# rpi-can-rs485.net
KiCad netlist of a schematic drawn in EAGLE
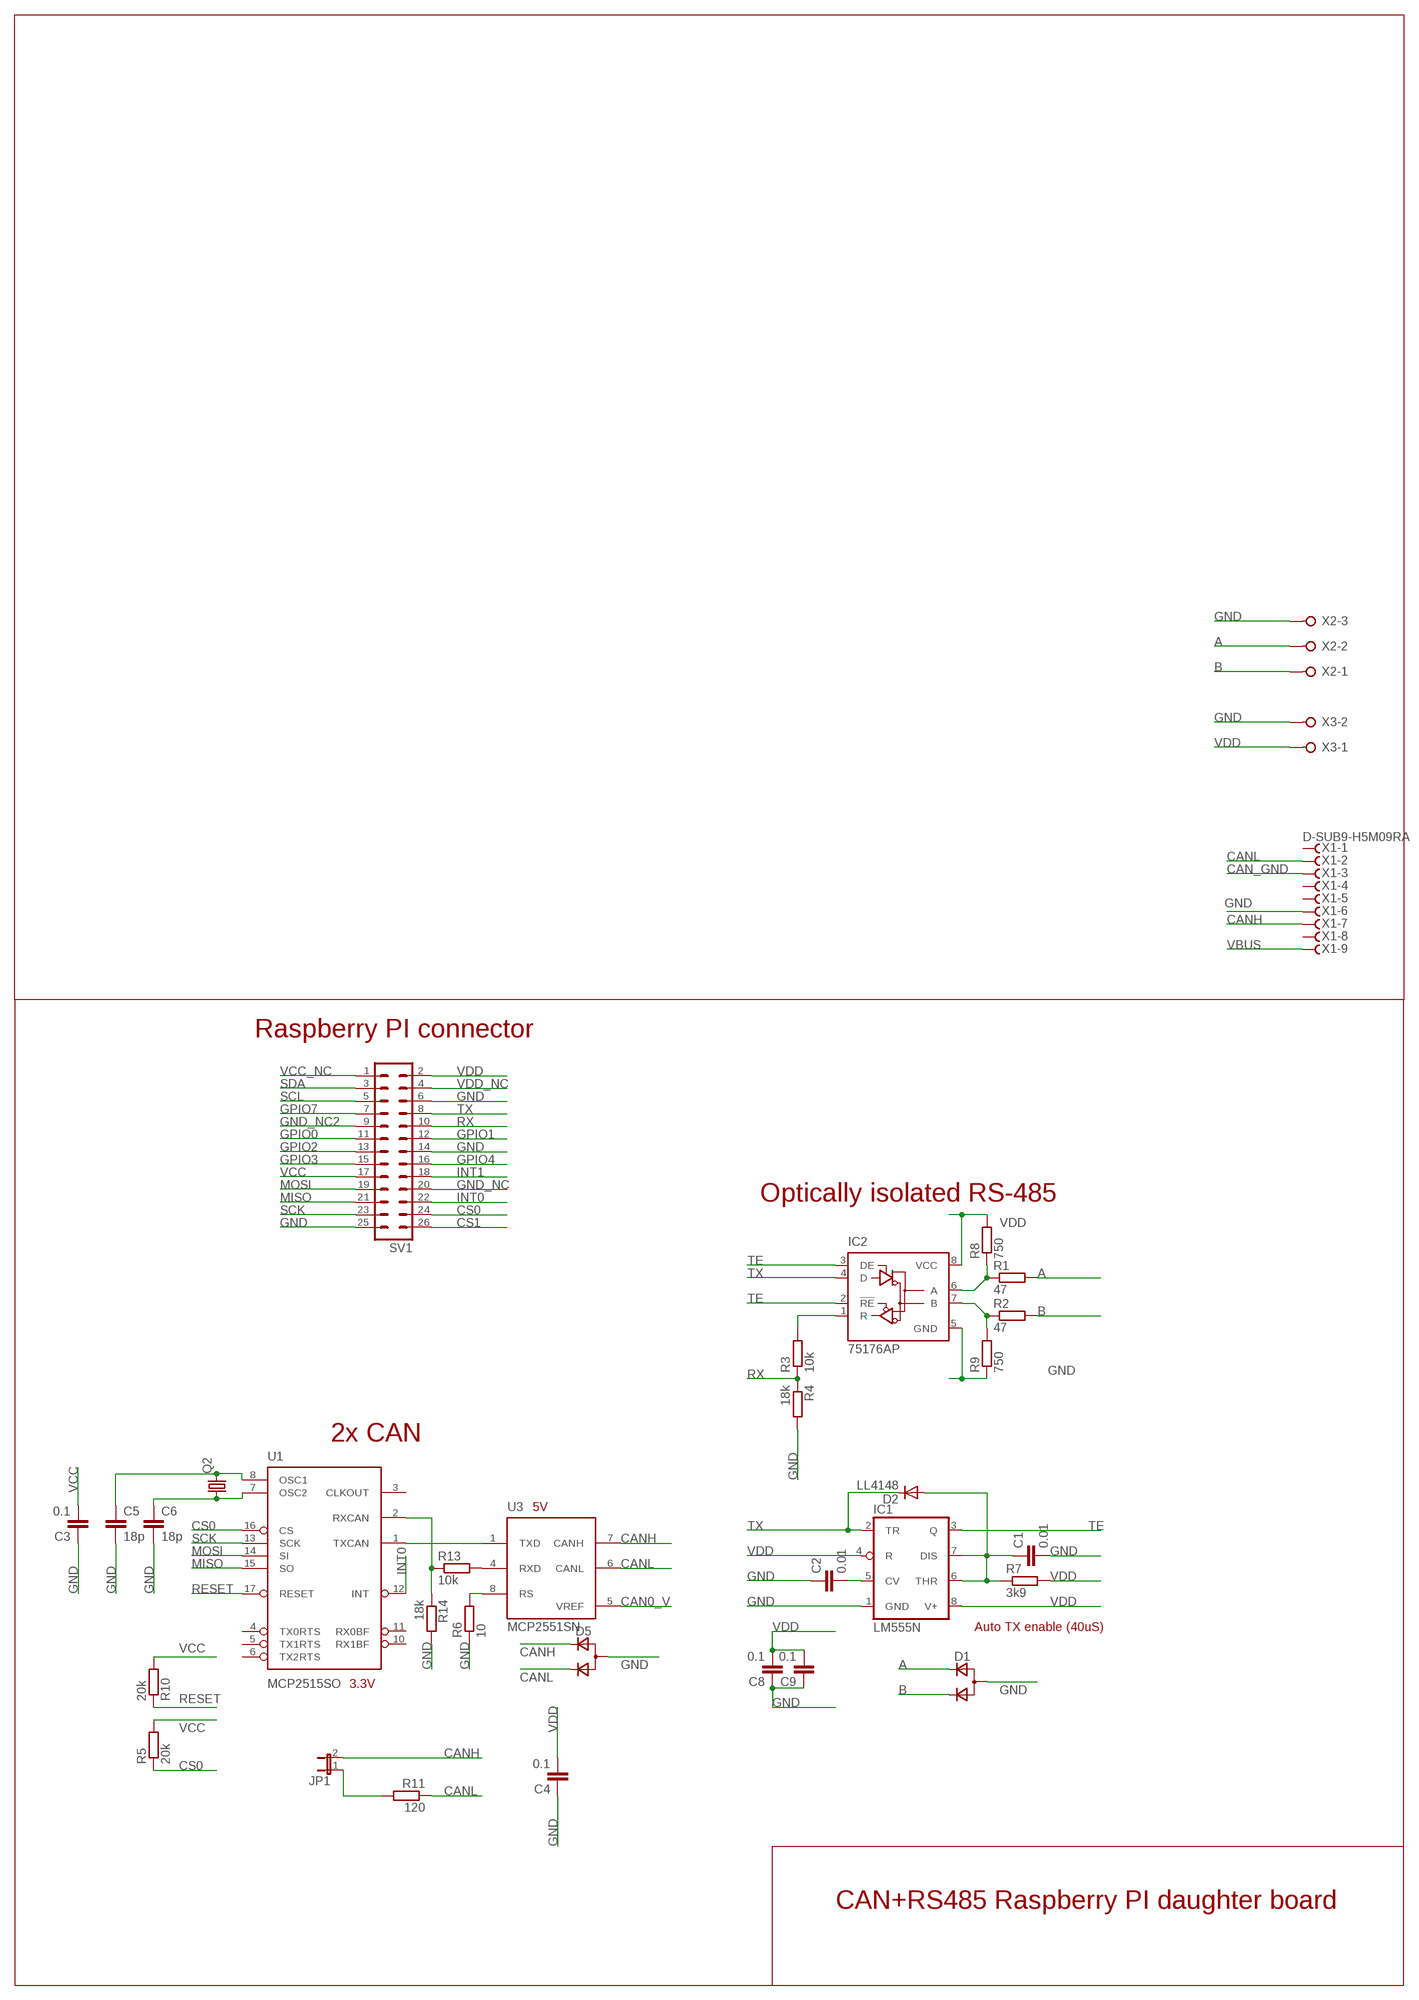
[diagram p0: schematic, sheet 1]

(export (version "E")
  (design (tool "Eeschema 10.0.6"))
  (components
    (comp (ref "C1")
      (value "0.01")
      (footprint "eagle-import:C0805")
      (libsource (lib "eagle-import") (part "C-EUC0805"))
    )
    (comp (ref "C2")
      (value "0.01")
      (footprint "eagle-import:C0805")
      (libsource (lib "eagle-import") (part "C-EUC0805"))
    )
    (comp (ref "C3")
      (value "0.1")
      (footprint "eagle-import:C0805")
      (libsource (lib "eagle-import") (part "C-EUC0805"))
    )
    (comp (ref "C4")
      (value "0.1")
      (footprint "eagle-import:C0805")
      (libsource (lib "eagle-import") (part "C-EUC0805"))
    )
    (comp (ref "C5")
      (value "18p")
      (footprint "eagle-import:C0805")
      (libsource (lib "eagle-import") (part "C-EUC0805"))
    )
    (comp (ref "C6")
      (value "18p")
      (footprint "eagle-import:C0805")
      (libsource (lib "eagle-import") (part "C-EUC0805"))
    )
    (comp (ref "C8")
      (value "0.1")
      (footprint "eagle-import:C0805")
      (libsource (lib "eagle-import") (part "C-EUC0805"))
    )
    (comp (ref "C9")
      (value "0.1")
      (footprint "eagle-import:C0805")
      (libsource (lib "eagle-import") (part "C-EUC0805"))
    )
    (comp (ref "D1")
      (value "D_2CSOT323")
      (footprint "eagle-import:SOT323")
      (libsource (lib "eagle-import") (part "D_2CSOT323"))
    )
    (comp (ref "D2")
      (value "LL4148")
      (footprint "eagle-import:SOD80C")
      (libsource (lib "eagle-import") (part "DIODE-SOD80C"))
    )
    (comp (ref "D5")
      (value "D_2CSOT323")
      (footprint "eagle-import:SOT323")
      (libsource (lib "eagle-import") (part "D_2CSOT323"))
    )
    (comp (ref "IC1")
      (value "LM555N")
      (footprint "eagle-import:DIL08")
      (libsource (lib "eagle-import") (part "555NLM"))
    )
    (comp (ref "IC2")
      (value "75176AP")
      (footprint "eagle-import:DIL08")
      (libsource (lib "eagle-import") (part "75176AP"))
    )
    (comp (ref "JP1")
      (value "JP1E")
      (footprint "eagle-import:JP1")
      (libsource (lib "eagle-import") (part "JP1E"))
    )
    (comp (ref "Q2")
      (value "CRYSTALHC49S")
      (footprint "eagle-import:HC49_S")
      (libsource (lib "eagle-import") (part "CRYSTALHC49S"))
    )
    (comp (ref "R1")
      (value "47")
      (footprint "eagle-import:R1206")
      (libsource (lib "eagle-import") (part "R-EU_R1206"))
    )
    (comp (ref "R2")
      (value "47")
      (footprint "eagle-import:R1206")
      (libsource (lib "eagle-import") (part "R-EU_R1206"))
    )
    (comp (ref "R3")
      (value "10k")
      (footprint "eagle-import:R0805")
      (libsource (lib "eagle-import") (part "R-EU_R0805"))
    )
    (comp (ref "R4")
      (value "18k")
      (footprint "eagle-import:R0805")
      (libsource (lib "eagle-import") (part "R-EU_R0805"))
    )
    (comp (ref "R5")
      (value "20k")
      (footprint "eagle-import:R0603")
      (libsource (lib "eagle-import") (part "R-EU_R0603"))
    )
    (comp (ref "R6")
      (value "10")
      (footprint "eagle-import:R0805")
      (libsource (lib "eagle-import") (part "R-EU_R0805"))
    )
    (comp (ref "R7")
      (value "3k9")
      (footprint "eagle-import:R0805")
      (libsource (lib "eagle-import") (part "R-EU_R0805"))
    )
    (comp (ref "R8")
      (value "750")
      (footprint "eagle-import:R1206")
      (libsource (lib "eagle-import") (part "R-EU_R1206"))
    )
    (comp (ref "R9")
      (value "750")
      (footprint "eagle-import:R1206")
      (libsource (lib "eagle-import") (part "R-EU_R1206"))
    )
    (comp (ref "R10")
      (value "20k")
      (footprint "eagle-import:R0805")
      (libsource (lib "eagle-import") (part "R-EU_R0805"))
    )
    (comp (ref "R11")
      (value "120")
      (footprint "eagle-import:R0805")
      (libsource (lib "eagle-import") (part "R-EU_R0805"))
    )
    (comp (ref "R13")
      (value "10k")
      (footprint "eagle-import:R0805")
      (libsource (lib "eagle-import") (part "R-EU_R0805"))
    )
    (comp (ref "R14")
      (value "18k")
      (footprint "eagle-import:R0805")
      (libsource (lib "eagle-import") (part "R-EU_R0805"))
    )
    (comp (ref "SV1")
      (value "MA13-2")
      (footprint "eagle-import:MA13-2")
      (libsource (lib "eagle-import") (part "MA13-2"))
    )
    (comp (ref "U1")
      (value "MCP2515SO")
      (footprint "eagle-import:SO-18W")
      (libsource (lib "eagle-import") (part "MCP2510SO"))
    )
    (comp (ref "U3")
      (value "MCP2551SN")
      (footprint "eagle-import:SO-08")
      (libsource (lib "eagle-import") (part "MCP2551SN"))
    )
    (comp (ref "X1")
      (value "D-SUB9-H5M09RA")
      (footprint "eagle-import:H5M09RA")
      (libsource (lib "eagle-import") (part "D-SUB9-H5M09RA"))
    )
    (comp (ref "X2")
      (value "W237-03P")
      (footprint "eagle-import:W237-133")
      (libsource (lib "eagle-import") (part "W237-03P"))
    )
    (comp (ref "X3")
      (value "W237-02P")
      (footprint "eagle-import:W237-132")
      (libsource (lib "eagle-import") (part "W237-02P"))
    )
  )
  (nets
    (net (code "1") (name "/A") (class "Default")
      (node (ref "D1") (pin "2") (pinfunction "C1_2") (pintype "passive"))
      (node (ref "R1") (pin "2") (pinfunction "2_2") (pintype "passive"))
      (node (ref "X2") (pin "2") (pinfunction "KL_2") (pintype "passive"))
    )
    (net (code "2") (name "/B") (class "Default")
      (node (ref "D1") (pin "3") (pinfunction "C2_3") (pintype "passive"))
      (node (ref "R2") (pin "2") (pinfunction "2_2") (pintype "passive"))
      (node (ref "X2") (pin "1") (pinfunction "KL_1") (pintype "passive"))
    )
    (net (code "3") (name "/CAN0_V") (class "Default")
      (node (ref "U3") (pin "5") (pinfunction "VREF_5") (pintype "power_in"))
    )
    (net (code "4") (name "/CANH") (class "Default")
      (node (ref "D5") (pin "2") (pinfunction "C1_2") (pintype "passive"))
      (node (ref "JP1") (pin "2") (pinfunction "2_2") (pintype "passive"))
      (node (ref "U3") (pin "7") (pinfunction "CANH_7") (pintype "bidirectional"))
      (node (ref "X1") (pin "7") (pinfunction "F_7") (pintype "passive"))
    )
    (net (code "5") (name "/CANL") (class "Default")
      (node (ref "D5") (pin "3") (pinfunction "C2_3") (pintype "passive"))
      (node (ref "R11") (pin "1") (pinfunction "1_1") (pintype "passive"))
      (node (ref "U3") (pin "6") (pinfunction "CANL_6") (pintype "bidirectional"))
      (node (ref "X1") (pin "2") (pinfunction "F_2") (pintype "passive"))
    )
    (net (code "6") (name "/CAN_GND") (class "Default")
      (node (ref "X1") (pin "3") (pinfunction "F_3") (pintype "passive"))
    )
    (net (code "7") (name "/CS0") (class "Default")
      (node (ref "R5") (pin "1") (pinfunction "1_1") (pintype "passive"))
      (node (ref "SV1") (pin "24") (pinfunction "24_24") (pintype "passive"))
      (node (ref "U1") (pin "16") (pinfunction "CS_16") (pintype "input"))
    )
    (net (code "8") (name "/CS1") (class "Default")
      (node (ref "SV1") (pin "26") (pinfunction "26_26") (pintype "passive"))
    )
    (net (code "9") (name "/GND") (class "Default")
      (node (ref "C1") (pin "2") (pinfunction "2_2") (pintype "passive"))
      (node (ref "C2") (pin "1") (pinfunction "1_1") (pintype "passive"))
      (node (ref "C3") (pin "1") (pinfunction "1_1") (pintype "passive"))
      (node (ref "C4") (pin "1") (pinfunction "1_1") (pintype "passive"))
      (node (ref "C5") (pin "2") (pinfunction "2_2") (pintype "passive"))
      (node (ref "C6") (pin "2") (pinfunction "2_2") (pintype "passive"))
      (node (ref "C8") (pin "1") (pinfunction "1_1") (pintype "passive"))
      (node (ref "C9") (pin "1") (pinfunction "1_1") (pintype "passive"))
      (node (ref "D1") (pin "1") (pinfunction "A_1") (pintype "passive"))
      (node (ref "D5") (pin "1") (pinfunction "A_1") (pintype "passive"))
      (node (ref "IC1") (pin "1") (pinfunction "GND_1") (pintype "power_in"))
      (node (ref "IC2") (pin "5") (pinfunction "GND_5") (pintype "power_in"))
      (node (ref "R14") (pin "2") (pinfunction "2_2") (pintype "passive"))
      (node (ref "R4") (pin "2") (pinfunction "2_2") (pintype "passive"))
      (node (ref "R6") (pin "1") (pinfunction "1_1") (pintype "passive"))
      (node (ref "R9") (pin "1") (pinfunction "1_1") (pintype "passive"))
      (node (ref "SV1") (pin "14") (pinfunction "14_14") (pintype "passive"))
      (node (ref "SV1") (pin "25") (pinfunction "25_25") (pintype "passive"))
      (node (ref "SV1") (pin "6") (pinfunction "6_6") (pintype "passive"))
      (node (ref "X1") (pin "6") (pinfunction "F_6") (pintype "passive"))
      (node (ref "X2") (pin "3") (pinfunction "KL_3") (pintype "passive"))
      (node (ref "X3") (pin "2") (pinfunction "KL_2") (pintype "passive"))
    )
    (net (code "10") (name "/GND_NC") (class "Default")
      (node (ref "SV1") (pin "20") (pinfunction "20_20") (pintype "passive"))
    )
    (net (code "11") (name "/GND_NC2") (class "Default")
      (node (ref "SV1") (pin "9") (pinfunction "9_9") (pintype "passive"))
    )
    (net (code "12") (name "/GPIO0") (class "Default")
      (node (ref "SV1") (pin "11") (pinfunction "11_11") (pintype "passive"))
    )
    (net (code "13") (name "/GPIO1") (class "Default")
      (node (ref "SV1") (pin "12") (pinfunction "12_12") (pintype "passive"))
    )
    (net (code "14") (name "/GPIO2") (class "Default")
      (node (ref "SV1") (pin "13") (pinfunction "13_13") (pintype "passive"))
    )
    (net (code "15") (name "/GPIO3") (class "Default")
      (node (ref "SV1") (pin "15") (pinfunction "15_15") (pintype "passive"))
    )
    (net (code "16") (name "/GPIO4") (class "Default")
      (node (ref "SV1") (pin "16") (pinfunction "16_16") (pintype "passive"))
    )
    (net (code "17") (name "/GPIO7") (class "Default")
      (node (ref "SV1") (pin "7") (pinfunction "7_7") (pintype "passive"))
    )
    (net (code "18") (name "/INT0") (class "Default")
      (node (ref "SV1") (pin "22") (pinfunction "22_22") (pintype "passive"))
      (node (ref "U1") (pin "12") (pinfunction "INT_12") (pintype "output"))
    )
    (net (code "19") (name "/INT1") (class "Default")
      (node (ref "SV1") (pin "18") (pinfunction "18_18") (pintype "passive"))
    )
    (net (code "20") (name "/MISO") (class "Default")
      (node (ref "SV1") (pin "21") (pinfunction "21_21") (pintype "passive"))
      (node (ref "U1") (pin "15") (pinfunction "SO_15") (pintype "output"))
    )
    (net (code "21") (name "/MOSI") (class "Default")
      (node (ref "SV1") (pin "19") (pinfunction "19_19") (pintype "passive"))
      (node (ref "U1") (pin "14") (pinfunction "SI_14") (pintype "input"))
    )
    (net (code "22") (name "/RESET") (class "Default")
      (node (ref "R10") (pin "1") (pinfunction "1_1") (pintype "passive"))
      (node (ref "U1") (pin "17") (pinfunction "RESET_17") (pintype "input"))
    )
    (net (code "23") (name "/RX") (class "Default")
      (node (ref "R3") (pin "1") (pinfunction "1_1") (pintype "passive"))
      (node (ref "R4") (pin "1") (pinfunction "1_1") (pintype "passive"))
      (node (ref "SV1") (pin "10") (pinfunction "10_10") (pintype "passive"))
    )
    (net (code "24") (name "/SCK") (class "Default")
      (node (ref "SV1") (pin "23") (pinfunction "23_23") (pintype "passive"))
      (node (ref "U1") (pin "13") (pinfunction "SCK_13") (pintype "input"))
    )
    (net (code "25") (name "/SCL") (class "Default")
      (node (ref "SV1") (pin "5") (pinfunction "5_5") (pintype "passive"))
    )
    (net (code "26") (name "/SDA") (class "Default")
      (node (ref "SV1") (pin "3") (pinfunction "3_3") (pintype "passive"))
    )
    (net (code "27") (name "/TE") (class "Default")
      (node (ref "IC1") (pin "3") (pinfunction "Q_3") (pintype "output"))
      (node (ref "IC2") (pin "2") (pinfunction "~{RE}_2") (pintype "input"))
      (node (ref "IC2") (pin "3") (pinfunction "DE_3") (pintype "input"))
    )
    (net (code "28") (name "/TX") (class "Default")
      (node (ref "D2") (pin "C") (pinfunction "C_C") (pintype "passive"))
      (node (ref "IC1") (pin "2") (pinfunction "TR_2") (pintype "input"))
      (node (ref "IC2") (pin "4") (pinfunction "D_4") (pintype "input"))
      (node (ref "SV1") (pin "8") (pinfunction "8_8") (pintype "passive"))
    )
    (net (code "29") (name "/VBUS") (class "Default")
      (node (ref "X1") (pin "9") (pinfunction "F_9") (pintype "passive"))
    )
    (net (code "30") (name "/VCC") (class "Default")
      (node (ref "C3") (pin "2") (pinfunction "2_2") (pintype "passive"))
      (node (ref "R10") (pin "2") (pinfunction "2_2") (pintype "passive"))
      (node (ref "R5") (pin "2") (pinfunction "2_2") (pintype "passive"))
      (node (ref "SV1") (pin "17") (pinfunction "17_17") (pintype "passive"))
    )
    (net (code "31") (name "/VCC_NC") (class "Default")
      (node (ref "SV1") (pin "1") (pinfunction "1_1") (pintype "passive"))
    )
    (net (code "32") (name "/VDD") (class "Default")
      (node (ref "C4") (pin "2") (pinfunction "2_2") (pintype "passive"))
      (node (ref "C8") (pin "2") (pinfunction "2_2") (pintype "passive"))
      (node (ref "C9") (pin "2") (pinfunction "2_2") (pintype "passive"))
      (node (ref "IC1") (pin "4") (pinfunction "R_4") (pintype "input"))
      (node (ref "IC1") (pin "8") (pinfunction "V+_8") (pintype "power_in"))
      (node (ref "IC2") (pin "8") (pinfunction "VCC_8") (pintype "power_in"))
      (node (ref "R7") (pin "2") (pinfunction "2_2") (pintype "passive"))
      (node (ref "R8") (pin "2") (pinfunction "2_2") (pintype "passive"))
      (node (ref "SV1") (pin "2") (pinfunction "2_2") (pintype "passive"))
      (node (ref "X3") (pin "1") (pinfunction "KL_1") (pintype "passive"))
    )
    (net (code "33") (name "/VDD_NC") (class "Default")
      (node (ref "SV1") (pin "4") (pinfunction "4_4") (pintype "passive"))
    )
    (net (code "34") (name "Net-(IC1-CV)") (class "Default")
      (node (ref "C2") (pin "2") (pinfunction "2_2") (pintype "passive"))
      (node (ref "IC1") (pin "5") (pinfunction "CV_5") (pintype "input"))
    )
    (net (code "35") (name "Net-(IC1-DIS)") (class "Default")
      (node (ref "C1") (pin "1") (pinfunction "1_1") (pintype "passive"))
      (node (ref "D2") (pin "A") (pinfunction "A_A") (pintype "passive"))
      (node (ref "IC1") (pin "6") (pinfunction "THR_6") (pintype "input"))
      (node (ref "IC1") (pin "7") (pinfunction "DIS_7") (pintype "input"))
      (node (ref "R7") (pin "1") (pinfunction "1_1") (pintype "passive"))
    )
    (net (code "36") (name "Net-(IC2-A)") (class "Default")
      (node (ref "IC2") (pin "6") (pinfunction "A_6") (pintype "output"))
      (node (ref "R1") (pin "1") (pinfunction "1_1") (pintype "passive"))
      (node (ref "R8") (pin "1") (pinfunction "1_1") (pintype "passive"))
    )
    (net (code "37") (name "Net-(IC2-B)") (class "Default")
      (node (ref "IC2") (pin "7") (pinfunction "B_7") (pintype "output"))
      (node (ref "R2") (pin "1") (pinfunction "1_1") (pintype "passive"))
      (node (ref "R9") (pin "2") (pinfunction "2_2") (pintype "passive"))
    )
    (net (code "38") (name "Net-(IC2-R)") (class "Default")
      (node (ref "IC2") (pin "1") (pinfunction "R_1") (pintype "input"))
      (node (ref "R3") (pin "2") (pinfunction "2_2") (pintype "passive"))
    )
    (net (code "39") (name "Net-(JP1-Pad1)") (class "Default")
      (node (ref "JP1") (pin "1") (pinfunction "1_1") (pintype "passive"))
      (node (ref "R11") (pin "2") (pinfunction "2_2") (pintype "passive"))
    )
    (net (code "40") (name "Net-(U1A-OSC1)") (class "Default")
      (node (ref "C5") (pin "1") (pinfunction "1_1") (pintype "passive"))
      (node (ref "Q2") (pin "2") (pinfunction "2_2") (pintype "passive"))
      (node (ref "U1") (pin "8") (pinfunction "OSC1_8") (pintype "input"))
    )
    (net (code "41") (name "Net-(U1A-OSC2)") (class "Default")
      (node (ref "C6") (pin "1") (pinfunction "1_1") (pintype "passive"))
      (node (ref "Q2") (pin "1") (pinfunction "1_1") (pintype "passive"))
      (node (ref "U1") (pin "7") (pinfunction "OSC2_7") (pintype "output"))
    )
    (net (code "42") (name "Net-(U1A-RXCAN)") (class "Default")
      (node (ref "R13") (pin "1") (pinfunction "1_1") (pintype "passive"))
      (node (ref "R14") (pin "1") (pinfunction "1_1") (pintype "passive"))
      (node (ref "U1") (pin "2") (pinfunction "RXCAN_2") (pintype "input"))
    )
    (net (code "43") (name "Net-(U1A-TXCAN)") (class "Default")
      (node (ref "U1") (pin "1") (pinfunction "TXCAN_1") (pintype "output"))
      (node (ref "U3") (pin "1") (pinfunction "TXD_1") (pintype "input"))
    )
    (net (code "44") (name "Net-(U3A-RS)") (class "Default")
      (node (ref "R6") (pin "2") (pinfunction "2_2") (pintype "passive"))
      (node (ref "U3") (pin "8") (pinfunction "RS_8") (pintype "input"))
    )
    (net (code "45") (name "Net-(U3A-RXD)") (class "Default")
      (node (ref "R13") (pin "2") (pinfunction "2_2") (pintype "passive"))
      (node (ref "U3") (pin "4") (pinfunction "RXD_4") (pintype "output"))
    )
    (net (code "46") (name "unconnected-(U1A-CLKOUT-Pad3)") (class "Default")
      (node (ref "U1") (pin "3") (pinfunction "CLKOUT_3") (pintype "output"))
    )
    (net (code "47") (name "unconnected-(U1A-RX0BF-Pad11)") (class "Default")
      (node (ref "U1") (pin "11") (pinfunction "RX0BF_11") (pintype "output"))
    )
    (net (code "48") (name "unconnected-(U1A-RX1BF-Pad10)") (class "Default")
      (node (ref "U1") (pin "10") (pinfunction "RX1BF_10") (pintype "output"))
    )
    (net (code "49") (name "unconnected-(U1A-TX0RTS-Pad4)") (class "Default")
      (node (ref "U1") (pin "4") (pinfunction "TX0RTS_4") (pintype "input"))
    )
    (net (code "50") (name "unconnected-(U1A-TX1RTS-Pad5)") (class "Default")
      (node (ref "U1") (pin "5") (pinfunction "TX1RTS_5") (pintype "input"))
    )
    (net (code "51") (name "unconnected-(U1A-TX2RTS-Pad6)") (class "Default")
      (node (ref "U1") (pin "6") (pinfunction "TX2RTS_6") (pintype "input"))
    )
    (net (code "52") (name "unconnected-(X1A-F-Pad1)") (class "Default")
      (node (ref "X1") (pin "1") (pinfunction "F_1") (pintype "passive"))
    )
    (net (code "53") (name "unconnected-(X1D-F-Pad4)") (class "Default")
      (node (ref "X1") (pin "4") (pinfunction "F_4") (pintype "passive"))
    )
    (net (code "54") (name "unconnected-(X1E-F-Pad5)") (class "Default")
      (node (ref "X1") (pin "5") (pinfunction "F_5") (pintype "passive"))
    )
    (net (code "55") (name "unconnected-(X1H-F-Pad8)") (class "Default")
      (node (ref "X1") (pin "8") (pinfunction "F_8") (pintype "passive"))
    )
  )
)
